# Home_Control.net
KiCad netlist of a schematic drawn in EAGLE
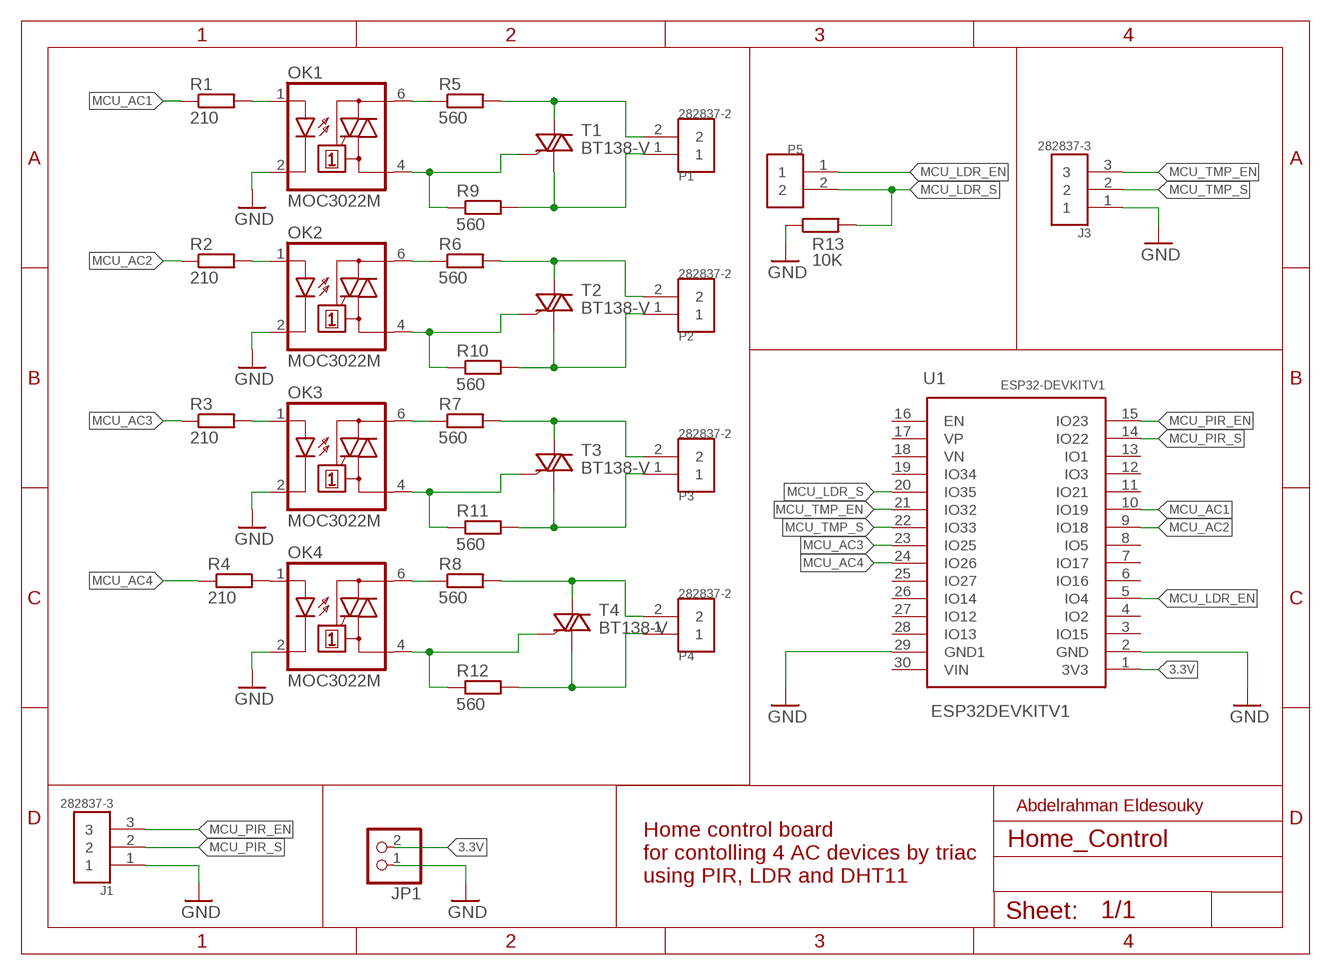
[diagram p0: schematic, sheet 1]

(export (version "E")
  (design (tool "Eeschema 10.0.6"))
  (components
    (comp (ref "J1")
      (value "282837-3")
      (footprint "eagle-import:TE_282837-3")
      (fields (field (name "MF") "TE Connectivity"))
      (libsource (lib "eagle-import") (part "282837-3"))
    )
    (comp (ref "J3")
      (value "282837-3")
      (footprint "eagle-import:TE_282837-3")
      (fields (field (name "MF") "TE Connectivity"))
      (libsource (lib "eagle-import") (part "282837-3"))
    )
    (comp (ref "JP1")
      (value "PINHD-1X2")
      (footprint "eagle-import:1X02")
      (libsource (lib "eagle-import") (part "PINHD-1X2"))
    )
    (comp (ref "OK1")
      (value "MOC3022M")
      (footprint "eagle-import:DIL06")
      (fields (field (name "MF") "FAIRCHILD SEMICONDUCTOR") (field (name "MPN") "MOC3022-M"))
      (libsource (lib "eagle-import") (part "MOC30M22"))
    )
    (comp (ref "OK2")
      (value "MOC3022M")
      (footprint "eagle-import:DIL06")
      (fields (field (name "MF") "FAIRCHILD SEMICONDUCTOR") (field (name "MPN") "MOC3022-M"))
      (libsource (lib "eagle-import") (part "MOC30M22"))
    )
    (comp (ref "OK3")
      (value "MOC3022M")
      (footprint "eagle-import:DIL06")
      (fields (field (name "MF") "FAIRCHILD SEMICONDUCTOR") (field (name "MPN") "MOC3022-M"))
      (libsource (lib "eagle-import") (part "MOC30M22"))
    )
    (comp (ref "OK4")
      (value "MOC3022M")
      (footprint "eagle-import:DIL06")
      (fields (field (name "MF") "FAIRCHILD SEMICONDUCTOR") (field (name "MPN") "MOC3022-M"))
      (libsource (lib "eagle-import") (part "MOC30M22"))
    )
    (comp (ref "P1")
      (value "282837-2")
      (footprint "eagle-import:TE_282837-2")
      (fields (field (name "MF") "TE Connectivity"))
      (libsource (lib "eagle-import") (part "282837-2"))
    )
    (comp (ref "P2")
      (value "282837-2")
      (footprint "eagle-import:TE_282837-2")
      (fields (field (name "MF") "TE Connectivity"))
      (libsource (lib "eagle-import") (part "282837-2"))
    )
    (comp (ref "P3")
      (value "282837-2")
      (footprint "eagle-import:TE_282837-2")
      (fields (field (name "MF") "TE Connectivity"))
      (libsource (lib "eagle-import") (part "282837-2"))
    )
    (comp (ref "P4")
      (value "282837-2")
      (footprint "eagle-import:TE_282837-2")
      (fields (field (name "MF") "TE Connectivity"))
      (libsource (lib "eagle-import") (part "282837-2"))
    )
    (comp (ref "P5")
      (value "282837-2")
      (footprint "eagle-import:TE_282837-2")
      (fields (field (name "MF") "TE Connectivity"))
      (libsource (lib "eagle-import") (part "282837-2"))
    )
    (comp (ref "R1")
      (value "210")
      (footprint "eagle-import:0411_15")
      (libsource (lib "eagle-import") (part "R-EU_0411/15"))
    )
    (comp (ref "R2")
      (value "210")
      (footprint "eagle-import:0411_15")
      (libsource (lib "eagle-import") (part "R-EU_0411/15"))
    )
    (comp (ref "R3")
      (value "210")
      (footprint "eagle-import:0411_15")
      (libsource (lib "eagle-import") (part "R-EU_0411/15"))
    )
    (comp (ref "R4")
      (value "210")
      (footprint "eagle-import:0411_15")
      (libsource (lib "eagle-import") (part "R-EU_0411/15"))
    )
    (comp (ref "R5")
      (value "560")
      (footprint "eagle-import:0411_15")
      (libsource (lib "eagle-import") (part "R-EU_0411/15"))
    )
    (comp (ref "R6")
      (value "560")
      (footprint "eagle-import:0411_15")
      (libsource (lib "eagle-import") (part "R-EU_0411/15"))
    )
    (comp (ref "R7")
      (value "560")
      (footprint "eagle-import:0411_15")
      (libsource (lib "eagle-import") (part "R-EU_0411/15"))
    )
    (comp (ref "R8")
      (value "560")
      (footprint "eagle-import:0411_15")
      (libsource (lib "eagle-import") (part "R-EU_0411/15"))
    )
    (comp (ref "R9")
      (value "560")
      (footprint "eagle-import:0411_15")
      (libsource (lib "eagle-import") (part "R-EU_0411/15"))
    )
    (comp (ref "R10")
      (value "560")
      (footprint "eagle-import:0411_15")
      (libsource (lib "eagle-import") (part "R-EU_0411/15"))
    )
    (comp (ref "R11")
      (value "560")
      (footprint "eagle-import:0411_15")
      (libsource (lib "eagle-import") (part "R-EU_0411/15"))
    )
    (comp (ref "R12")
      (value "560")
      (footprint "eagle-import:0411_15")
      (libsource (lib "eagle-import") (part "R-EU_0411/15"))
    )
    (comp (ref "R13")
      (value "10K")
      (footprint "eagle-import:0411_15")
      (libsource (lib "eagle-import") (part "R-EU_0411/15"))
    )
    (comp (ref "T1")
      (value "BT138-V")
      (footprint "eagle-import:TO220BV")
      (libsource (lib "eagle-import") (part "BT138-V"))
    )
    (comp (ref "T2")
      (value "BT138-V")
      (footprint "eagle-import:TO220BV")
      (libsource (lib "eagle-import") (part "BT138-V"))
    )
    (comp (ref "T3")
      (value "BT138-V")
      (footprint "eagle-import:TO220BV")
      (libsource (lib "eagle-import") (part "BT138-V"))
    )
    (comp (ref "T4")
      (value "BT138-V")
      (footprint "eagle-import:TO220BV")
      (libsource (lib "eagle-import") (part "BT138-V"))
    )
    (comp (ref "U1")
      (value "ESP32DEVKITV1")
      (footprint "eagle-import:ESP32-DEVKITV1")
      (libsource (lib "eagle-import") (part "ESP32DEVKITV1"))
    )
  )
  (nets
    (net (code "1") (name "3.3V") (class "Default")
      (node (ref "JP1") (pin "2") (pinfunction "2_2") (pintype "passive"))
      (node (ref "U1") (pin "1") (pinfunction "3V3_1") (pintype "bidirectional"))
    )
    (net (code "2") (name "GND") (class "Default")
      (node (ref "J1") (pin "1") (pinfunction "1_1") (pintype "passive"))
      (node (ref "J3") (pin "1") (pinfunction "1_1") (pintype "passive"))
      (node (ref "JP1") (pin "1") (pinfunction "1_1") (pintype "passive"))
      (node (ref "OK1") (pin "2") (pinfunction "C_2") (pintype "passive"))
      (node (ref "OK2") (pin "2") (pinfunction "C_2") (pintype "passive"))
      (node (ref "OK3") (pin "2") (pinfunction "C_2") (pintype "passive"))
      (node (ref "OK4") (pin "2") (pinfunction "C_2") (pintype "passive"))
      (node (ref "R13") (pin "1") (pinfunction "1_1") (pintype "passive"))
      (node (ref "U1") (pin "2") (pinfunction "GND_2") (pintype "bidirectional"))
      (node (ref "U1") (pin "29") (pinfunction "GND1_29") (pintype "bidirectional"))
    )
    (net (code "3") (name "MCU_AC1") (class "Default")
      (node (ref "R1") (pin "1") (pinfunction "1_1") (pintype "passive"))
      (node (ref "U1") (pin "10") (pinfunction "IO19_10") (pintype "bidirectional"))
    )
    (net (code "4") (name "MCU_AC2") (class "Default")
      (node (ref "R2") (pin "1") (pinfunction "1_1") (pintype "passive"))
      (node (ref "U1") (pin "9") (pinfunction "IO18_9") (pintype "bidirectional"))
    )
    (net (code "5") (name "MCU_AC3") (class "Default")
      (node (ref "R3") (pin "1") (pinfunction "1_1") (pintype "passive"))
      (node (ref "U1") (pin "23") (pinfunction "IO25_23") (pintype "bidirectional"))
    )
    (net (code "6") (name "MCU_AC4") (class "Default")
      (node (ref "R4") (pin "1") (pinfunction "1_1") (pintype "passive"))
      (node (ref "U1") (pin "24") (pinfunction "IO26_24") (pintype "bidirectional"))
    )
    (net (code "7") (name "MCU_LDR_EN") (class "Default")
      (node (ref "P5") (pin "1") (pinfunction "1_1") (pintype "passive"))
      (node (ref "U1") (pin "5") (pinfunction "IO4_5") (pintype "bidirectional"))
    )
    (net (code "8") (name "MCU_LDR_S") (class "Default")
      (node (ref "P5") (pin "2") (pinfunction "2_2") (pintype "passive"))
      (node (ref "R13") (pin "2") (pinfunction "2_2") (pintype "passive"))
      (node (ref "U1") (pin "20") (pinfunction "IO35_20") (pintype "bidirectional"))
    )
    (net (code "9") (name "MCU_PIR_EN") (class "Default")
      (node (ref "J1") (pin "3") (pinfunction "3_3") (pintype "passive"))
      (node (ref "U1") (pin "15") (pinfunction "IO23_15") (pintype "bidirectional"))
    )
    (net (code "10") (name "MCU_PIR_S") (class "Default")
      (node (ref "J1") (pin "2") (pinfunction "2_2") (pintype "passive"))
      (node (ref "U1") (pin "14") (pinfunction "IO22_14") (pintype "bidirectional"))
    )
    (net (code "11") (name "MCU_TMP_EN") (class "Default")
      (node (ref "J3") (pin "3") (pinfunction "3_3") (pintype "passive"))
      (node (ref "U1") (pin "21") (pinfunction "IO32_21") (pintype "bidirectional"))
    )
    (net (code "12") (name "MCU_TMP_S") (class "Default")
      (node (ref "J3") (pin "2") (pinfunction "2_2") (pintype "passive"))
      (node (ref "U1") (pin "22") (pinfunction "IO33_22") (pintype "bidirectional"))
    )
    (net (code "13") (name "Net-(OK1-A)") (class "Default")
      (node (ref "OK1") (pin "1") (pinfunction "A_1") (pintype "passive"))
      (node (ref "R1") (pin "2") (pinfunction "2_2") (pintype "passive"))
    )
    (net (code "14") (name "Net-(OK1-A1)") (class "Default")
      (node (ref "OK1") (pin "4") (pinfunction "A1_4") (pintype "passive"))
      (node (ref "R9") (pin "1") (pinfunction "1_1") (pintype "passive"))
      (node (ref "T1") (pin "G") (pinfunction "G_G") (pintype "passive"))
    )
    (net (code "15") (name "Net-(OK1-A2)") (class "Default")
      (node (ref "OK1") (pin "6") (pinfunction "A2_6") (pintype "passive"))
      (node (ref "R5") (pin "1") (pinfunction "1_1") (pintype "passive"))
    )
    (net (code "16") (name "Net-(OK2-A)") (class "Default")
      (node (ref "OK2") (pin "1") (pinfunction "A_1") (pintype "passive"))
      (node (ref "R2") (pin "2") (pinfunction "2_2") (pintype "passive"))
    )
    (net (code "17") (name "Net-(OK2-A1)") (class "Default")
      (node (ref "OK2") (pin "4") (pinfunction "A1_4") (pintype "passive"))
      (node (ref "R10") (pin "1") (pinfunction "1_1") (pintype "passive"))
      (node (ref "T2") (pin "G") (pinfunction "G_G") (pintype "passive"))
    )
    (net (code "18") (name "Net-(OK2-A2)") (class "Default")
      (node (ref "OK2") (pin "6") (pinfunction "A2_6") (pintype "passive"))
      (node (ref "R6") (pin "1") (pinfunction "1_1") (pintype "passive"))
    )
    (net (code "19") (name "Net-(OK3-A)") (class "Default")
      (node (ref "OK3") (pin "1") (pinfunction "A_1") (pintype "passive"))
      (node (ref "R3") (pin "2") (pinfunction "2_2") (pintype "passive"))
    )
    (net (code "20") (name "Net-(OK3-A1)") (class "Default")
      (node (ref "OK3") (pin "4") (pinfunction "A1_4") (pintype "passive"))
      (node (ref "R11") (pin "1") (pinfunction "1_1") (pintype "passive"))
      (node (ref "T3") (pin "G") (pinfunction "G_G") (pintype "passive"))
    )
    (net (code "21") (name "Net-(OK3-A2)") (class "Default")
      (node (ref "OK3") (pin "6") (pinfunction "A2_6") (pintype "passive"))
      (node (ref "R7") (pin "1") (pinfunction "1_1") (pintype "passive"))
    )
    (net (code "22") (name "Net-(OK4-A)") (class "Default")
      (node (ref "OK4") (pin "1") (pinfunction "A_1") (pintype "passive"))
      (node (ref "R4") (pin "2") (pinfunction "2_2") (pintype "passive"))
    )
    (net (code "23") (name "Net-(OK4-A1)") (class "Default")
      (node (ref "OK4") (pin "4") (pinfunction "A1_4") (pintype "passive"))
      (node (ref "R12") (pin "1") (pinfunction "1_1") (pintype "passive"))
      (node (ref "T4") (pin "G") (pinfunction "G_G") (pintype "passive"))
    )
    (net (code "24") (name "Net-(OK4-A2)") (class "Default")
      (node (ref "OK4") (pin "6") (pinfunction "A2_6") (pintype "passive"))
      (node (ref "R8") (pin "1") (pinfunction "1_1") (pintype "passive"))
    )
    (net (code "25") (name "Net-(T1-A1)") (class "Default")
      (node (ref "P1") (pin "1") (pinfunction "1_1") (pintype "passive"))
      (node (ref "R9") (pin "2") (pinfunction "2_2") (pintype "passive"))
      (node (ref "T1") (pin "T1") (pinfunction "A1_T1") (pintype "passive"))
    )
    (net (code "26") (name "Net-(T1-A2)") (class "Default")
      (node (ref "P1") (pin "2") (pinfunction "2_2") (pintype "passive"))
      (node (ref "R5") (pin "2") (pinfunction "2_2") (pintype "passive"))
      (node (ref "T1") (pin "T2") (pinfunction "A2_T2") (pintype "passive"))
    )
    (net (code "27") (name "Net-(T2-A1)") (class "Default")
      (node (ref "P2") (pin "1") (pinfunction "1_1") (pintype "passive"))
      (node (ref "R10") (pin "2") (pinfunction "2_2") (pintype "passive"))
      (node (ref "T2") (pin "T1") (pinfunction "A1_T1") (pintype "passive"))
    )
    (net (code "28") (name "Net-(T2-A2)") (class "Default")
      (node (ref "P2") (pin "2") (pinfunction "2_2") (pintype "passive"))
      (node (ref "R6") (pin "2") (pinfunction "2_2") (pintype "passive"))
      (node (ref "T2") (pin "T2") (pinfunction "A2_T2") (pintype "passive"))
    )
    (net (code "29") (name "Net-(T3-A1)") (class "Default")
      (node (ref "P3") (pin "1") (pinfunction "1_1") (pintype "passive"))
      (node (ref "R11") (pin "2") (pinfunction "2_2") (pintype "passive"))
      (node (ref "T3") (pin "T1") (pinfunction "A1_T1") (pintype "passive"))
    )
    (net (code "30") (name "Net-(T3-A2)") (class "Default")
      (node (ref "P3") (pin "2") (pinfunction "2_2") (pintype "passive"))
      (node (ref "R7") (pin "2") (pinfunction "2_2") (pintype "passive"))
      (node (ref "T3") (pin "T2") (pinfunction "A2_T2") (pintype "passive"))
    )
    (net (code "31") (name "Net-(T4-A1)") (class "Default")
      (node (ref "P4") (pin "1") (pinfunction "1_1") (pintype "passive"))
      (node (ref "R12") (pin "2") (pinfunction "2_2") (pintype "passive"))
      (node (ref "T4") (pin "T1") (pinfunction "A1_T1") (pintype "passive"))
    )
    (net (code "32") (name "Net-(T4-A2)") (class "Default")
      (node (ref "P4") (pin "2") (pinfunction "2_2") (pintype "passive"))
      (node (ref "R8") (pin "2") (pinfunction "2_2") (pintype "passive"))
      (node (ref "T4") (pin "T2") (pinfunction "A2_T2") (pintype "passive"))
    )
    (net (code "33") (name "unconnected-(U1-EN-Pad16)") (class "Default")
      (node (ref "U1") (pin "16") (pinfunction "EN_16") (pintype "bidirectional"))
    )
    (net (code "34") (name "unconnected-(U1-IO1-Pad13)") (class "Default")
      (node (ref "U1") (pin "13") (pinfunction "IO1_13") (pintype "bidirectional"))
    )
    (net (code "35") (name "unconnected-(U1-IO2-Pad4)") (class "Default")
      (node (ref "U1") (pin "4") (pinfunction "IO2_4") (pintype "bidirectional"))
    )
    (net (code "36") (name "unconnected-(U1-IO3-Pad12)") (class "Default")
      (node (ref "U1") (pin "12") (pinfunction "IO3_12") (pintype "bidirectional"))
    )
    (net (code "37") (name "unconnected-(U1-IO5-Pad8)") (class "Default")
      (node (ref "U1") (pin "8") (pinfunction "IO5_8") (pintype "bidirectional"))
    )
    (net (code "38") (name "unconnected-(U1-IO12-Pad27)") (class "Default")
      (node (ref "U1") (pin "27") (pinfunction "IO12_27") (pintype "bidirectional"))
    )
    (net (code "39") (name "unconnected-(U1-IO13-Pad28)") (class "Default")
      (node (ref "U1") (pin "28") (pinfunction "IO13_28") (pintype "bidirectional"))
    )
    (net (code "40") (name "unconnected-(U1-IO14-Pad26)") (class "Default")
      (node (ref "U1") (pin "26") (pinfunction "IO14_26") (pintype "bidirectional"))
    )
    (net (code "41") (name "unconnected-(U1-IO15-Pad3)") (class "Default")
      (node (ref "U1") (pin "3") (pinfunction "IO15_3") (pintype "bidirectional"))
    )
    (net (code "42") (name "unconnected-(U1-IO16-Pad6)") (class "Default")
      (node (ref "U1") (pin "6") (pinfunction "IO16_6") (pintype "bidirectional"))
    )
    (net (code "43") (name "unconnected-(U1-IO17-Pad7)") (class "Default")
      (node (ref "U1") (pin "7") (pinfunction "IO17_7") (pintype "bidirectional"))
    )
    (net (code "44") (name "unconnected-(U1-IO21-Pad11)") (class "Default")
      (node (ref "U1") (pin "11") (pinfunction "IO21_11") (pintype "bidirectional"))
    )
    (net (code "45") (name "unconnected-(U1-IO27-Pad25)") (class "Default")
      (node (ref "U1") (pin "25") (pinfunction "IO27_25") (pintype "bidirectional"))
    )
    (net (code "46") (name "unconnected-(U1-IO34-Pad19)") (class "Default")
      (node (ref "U1") (pin "19") (pinfunction "IO34_19") (pintype "bidirectional"))
    )
    (net (code "47") (name "unconnected-(U1-VIN-Pad30)") (class "Default")
      (node (ref "U1") (pin "30") (pinfunction "VIN_30") (pintype "bidirectional"))
    )
    (net (code "48") (name "unconnected-(U1-VN-Pad18)") (class "Default")
      (node (ref "U1") (pin "18") (pinfunction "VN_18") (pintype "bidirectional"))
    )
    (net (code "49") (name "unconnected-(U1-VP-Pad17)") (class "Default")
      (node (ref "U1") (pin "17") (pinfunction "VP_17") (pintype "bidirectional"))
    )
  )
)
